# 8_RGB_SMD_LEDs.net
KiCad netlist of a schematic drawn in EAGLE
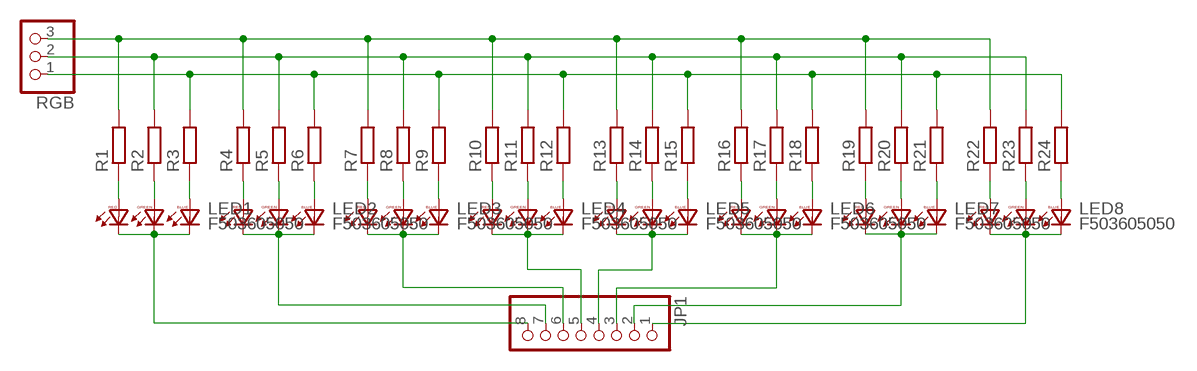
[diagram p0: schematic, sheet 1]

(export (version "E")
  (design (tool "Eeschema 10.0.6"))
  (components
    (comp (ref "JP1")
      (value "PINHD-1X8")
      (footprint "eagle-import:1X08")
      (libsource (lib "eagle-import") (part "PINHD-1X8"))
    )
    (comp (ref "LED1")
      (value "F503605050")
      (footprint "eagle-import:5050LED")
      (libsource (lib "eagle-import") (part "F503605050"))
    )
    (comp (ref "LED2")
      (value "F503605050")
      (footprint "eagle-import:5050LED")
      (libsource (lib "eagle-import") (part "F503605050"))
    )
    (comp (ref "LED3")
      (value "F503605050")
      (footprint "eagle-import:5050LED")
      (libsource (lib "eagle-import") (part "F503605050"))
    )
    (comp (ref "LED4")
      (value "F503605050")
      (footprint "eagle-import:5050LED")
      (libsource (lib "eagle-import") (part "F503605050"))
    )
    (comp (ref "LED5")
      (value "F503605050")
      (footprint "eagle-import:5050LED")
      (libsource (lib "eagle-import") (part "F503605050"))
    )
    (comp (ref "LED6")
      (value "F503605050")
      (footprint "eagle-import:5050LED")
      (libsource (lib "eagle-import") (part "F503605050"))
    )
    (comp (ref "LED7")
      (value "F503605050")
      (footprint "eagle-import:5050LED")
      (libsource (lib "eagle-import") (part "F503605050"))
    )
    (comp (ref "LED8")
      (value "F503605050")
      (footprint "eagle-import:5050LED")
      (libsource (lib "eagle-import") (part "F503605050"))
    )
    (comp (ref "R1")
      (value "R-EU_0207/7")
      (footprint "eagle-import:0207_7")
      (libsource (lib "eagle-import") (part "R-EU_0207/7"))
    )
    (comp (ref "R2")
      (value "R-EU_0207/7")
      (footprint "eagle-import:0207_7")
      (libsource (lib "eagle-import") (part "R-EU_0207/7"))
    )
    (comp (ref "R3")
      (value "R-EU_0207/7")
      (footprint "eagle-import:0207_7")
      (libsource (lib "eagle-import") (part "R-EU_0207/7"))
    )
    (comp (ref "R4")
      (value "R-EU_0207/7")
      (footprint "eagle-import:0207_7")
      (libsource (lib "eagle-import") (part "R-EU_0207/7"))
    )
    (comp (ref "R5")
      (value "R-EU_0207/7")
      (footprint "eagle-import:0207_7")
      (libsource (lib "eagle-import") (part "R-EU_0207/7"))
    )
    (comp (ref "R6")
      (value "R-EU_0207/7")
      (footprint "eagle-import:0207_7")
      (libsource (lib "eagle-import") (part "R-EU_0207/7"))
    )
    (comp (ref "R7")
      (value "R-EU_0207/7")
      (footprint "eagle-import:0207_7")
      (libsource (lib "eagle-import") (part "R-EU_0207/7"))
    )
    (comp (ref "R8")
      (value "R-EU_0207/7")
      (footprint "eagle-import:0207_7")
      (libsource (lib "eagle-import") (part "R-EU_0207/7"))
    )
    (comp (ref "R9")
      (value "R-EU_0207/7")
      (footprint "eagle-import:0207_7")
      (libsource (lib "eagle-import") (part "R-EU_0207/7"))
    )
    (comp (ref "R10")
      (value "R-EU_0207/7")
      (footprint "eagle-import:0207_7")
      (libsource (lib "eagle-import") (part "R-EU_0207/7"))
    )
    (comp (ref "R11")
      (value "R-EU_0207/7")
      (footprint "eagle-import:0207_7")
      (libsource (lib "eagle-import") (part "R-EU_0207/7"))
    )
    (comp (ref "R12")
      (value "R-EU_0207/7")
      (footprint "eagle-import:0207_7")
      (libsource (lib "eagle-import") (part "R-EU_0207/7"))
    )
    (comp (ref "R13")
      (value "R-EU_0207/7")
      (footprint "eagle-import:0207_7")
      (libsource (lib "eagle-import") (part "R-EU_0207/7"))
    )
    (comp (ref "R14")
      (value "R-EU_0207/7")
      (footprint "eagle-import:0207_7")
      (libsource (lib "eagle-import") (part "R-EU_0207/7"))
    )
    (comp (ref "R15")
      (value "R-EU_0207/7")
      (footprint "eagle-import:0207_7")
      (libsource (lib "eagle-import") (part "R-EU_0207/7"))
    )
    (comp (ref "R16")
      (value "R-EU_0207/7")
      (footprint "eagle-import:0207_7")
      (libsource (lib "eagle-import") (part "R-EU_0207/7"))
    )
    (comp (ref "R17")
      (value "R-EU_0207/7")
      (footprint "eagle-import:0207_7")
      (libsource (lib "eagle-import") (part "R-EU_0207/7"))
    )
    (comp (ref "R18")
      (value "R-EU_0207/7")
      (footprint "eagle-import:0207_7")
      (libsource (lib "eagle-import") (part "R-EU_0207/7"))
    )
    (comp (ref "R19")
      (value "R-EU_0207/7")
      (footprint "eagle-import:0207_7")
      (libsource (lib "eagle-import") (part "R-EU_0207/7"))
    )
    (comp (ref "R20")
      (value "R-EU_0207/7")
      (footprint "eagle-import:0207_7")
      (libsource (lib "eagle-import") (part "R-EU_0207/7"))
    )
    (comp (ref "R21")
      (value "R-EU_0207/7")
      (footprint "eagle-import:0207_7")
      (libsource (lib "eagle-import") (part "R-EU_0207/7"))
    )
    (comp (ref "R22")
      (value "R-EU_0207/7")
      (footprint "eagle-import:0207_7")
      (libsource (lib "eagle-import") (part "R-EU_0207/7"))
    )
    (comp (ref "R23")
      (value "R-EU_0207/7")
      (footprint "eagle-import:0207_7")
      (libsource (lib "eagle-import") (part "R-EU_0207/7"))
    )
    (comp (ref "R24")
      (value "R-EU_0207/7")
      (footprint "eagle-import:0207_7")
      (libsource (lib "eagle-import") (part "R-EU_0207/7"))
    )
    (comp (ref "RGB")
      (value "PINHD-1X3")
      (footprint "eagle-import:1X03")
      (libsource (lib "eagle-import") (part "PINHD-1X3"))
    )
  )
  (nets
    (net (code "1") (name "Net-(LED1-BA)") (class "Default")
      (node (ref "LED1") (pin "B1") (pinfunction "BA_B1") (pintype "passive"))
      (node (ref "R3") (pin "1") (pinfunction "1_1") (pintype "passive"))
    )
    (net (code "2") (name "Net-(LED1-BC)") (class "Default")
      (node (ref "JP1") (pin "8") (pinfunction "8_8") (pintype "passive"))
      (node (ref "LED1") (pin "B2") (pinfunction "BC_B2") (pintype "passive"))
      (node (ref "LED1") (pin "G2") (pinfunction "GC_G2") (pintype "passive"))
      (node (ref "LED1") (pin "R2") (pinfunction "RC_R2") (pintype "passive"))
    )
    (net (code "3") (name "Net-(LED1-GA)") (class "Default")
      (node (ref "LED1") (pin "G1") (pinfunction "GA_G1") (pintype "passive"))
      (node (ref "R2") (pin "1") (pinfunction "1_1") (pintype "passive"))
    )
    (net (code "4") (name "Net-(LED1-RA)") (class "Default")
      (node (ref "LED1") (pin "R1") (pinfunction "RA_R1") (pintype "passive"))
      (node (ref "R1") (pin "1") (pinfunction "1_1") (pintype "passive"))
    )
    (net (code "5") (name "Net-(LED2-BA)") (class "Default")
      (node (ref "LED2") (pin "B1") (pinfunction "BA_B1") (pintype "passive"))
      (node (ref "R6") (pin "1") (pinfunction "1_1") (pintype "passive"))
    )
    (net (code "6") (name "Net-(LED2-BC)") (class "Default")
      (node (ref "JP1") (pin "7") (pinfunction "7_7") (pintype "passive"))
      (node (ref "LED2") (pin "B2") (pinfunction "BC_B2") (pintype "passive"))
      (node (ref "LED2") (pin "G2") (pinfunction "GC_G2") (pintype "passive"))
      (node (ref "LED2") (pin "R2") (pinfunction "RC_R2") (pintype "passive"))
    )
    (net (code "7") (name "Net-(LED2-GA)") (class "Default")
      (node (ref "LED2") (pin "G1") (pinfunction "GA_G1") (pintype "passive"))
      (node (ref "R5") (pin "1") (pinfunction "1_1") (pintype "passive"))
    )
    (net (code "8") (name "Net-(LED2-RA)") (class "Default")
      (node (ref "LED2") (pin "R1") (pinfunction "RA_R1") (pintype "passive"))
      (node (ref "R4") (pin "1") (pinfunction "1_1") (pintype "passive"))
    )
    (net (code "9") (name "Net-(LED3-BA)") (class "Default")
      (node (ref "LED3") (pin "B1") (pinfunction "BA_B1") (pintype "passive"))
      (node (ref "R9") (pin "1") (pinfunction "1_1") (pintype "passive"))
    )
    (net (code "10") (name "Net-(LED3-BC)") (class "Default")
      (node (ref "JP1") (pin "6") (pinfunction "6_6") (pintype "passive"))
      (node (ref "LED3") (pin "B2") (pinfunction "BC_B2") (pintype "passive"))
      (node (ref "LED3") (pin "G2") (pinfunction "GC_G2") (pintype "passive"))
      (node (ref "LED3") (pin "R2") (pinfunction "RC_R2") (pintype "passive"))
    )
    (net (code "11") (name "Net-(LED3-GA)") (class "Default")
      (node (ref "LED3") (pin "G1") (pinfunction "GA_G1") (pintype "passive"))
      (node (ref "R8") (pin "1") (pinfunction "1_1") (pintype "passive"))
    )
    (net (code "12") (name "Net-(LED3-RA)") (class "Default")
      (node (ref "LED3") (pin "R1") (pinfunction "RA_R1") (pintype "passive"))
      (node (ref "R7") (pin "1") (pinfunction "1_1") (pintype "passive"))
    )
    (net (code "13") (name "Net-(LED4-BA)") (class "Default")
      (node (ref "LED4") (pin "B1") (pinfunction "BA_B1") (pintype "passive"))
      (node (ref "R12") (pin "1") (pinfunction "1_1") (pintype "passive"))
    )
    (net (code "14") (name "Net-(LED4-BC)") (class "Default")
      (node (ref "JP1") (pin "5") (pinfunction "5_5") (pintype "passive"))
      (node (ref "LED4") (pin "B2") (pinfunction "BC_B2") (pintype "passive"))
      (node (ref "LED4") (pin "G2") (pinfunction "GC_G2") (pintype "passive"))
      (node (ref "LED4") (pin "R2") (pinfunction "RC_R2") (pintype "passive"))
    )
    (net (code "15") (name "Net-(LED4-GA)") (class "Default")
      (node (ref "LED4") (pin "G1") (pinfunction "GA_G1") (pintype "passive"))
      (node (ref "R11") (pin "1") (pinfunction "1_1") (pintype "passive"))
    )
    (net (code "16") (name "Net-(LED4-RA)") (class "Default")
      (node (ref "LED4") (pin "R1") (pinfunction "RA_R1") (pintype "passive"))
      (node (ref "R10") (pin "1") (pinfunction "1_1") (pintype "passive"))
    )
    (net (code "17") (name "Net-(LED5-BA)") (class "Default")
      (node (ref "LED5") (pin "B1") (pinfunction "BA_B1") (pintype "passive"))
      (node (ref "R15") (pin "1") (pinfunction "1_1") (pintype "passive"))
    )
    (net (code "18") (name "Net-(LED5-BC)") (class "Default")
      (node (ref "JP1") (pin "4") (pinfunction "4_4") (pintype "passive"))
      (node (ref "LED5") (pin "B2") (pinfunction "BC_B2") (pintype "passive"))
      (node (ref "LED5") (pin "G2") (pinfunction "GC_G2") (pintype "passive"))
      (node (ref "LED5") (pin "R2") (pinfunction "RC_R2") (pintype "passive"))
    )
    (net (code "19") (name "Net-(LED5-GA)") (class "Default")
      (node (ref "LED5") (pin "G1") (pinfunction "GA_G1") (pintype "passive"))
      (node (ref "R14") (pin "1") (pinfunction "1_1") (pintype "passive"))
    )
    (net (code "20") (name "Net-(LED5-RA)") (class "Default")
      (node (ref "LED5") (pin "R1") (pinfunction "RA_R1") (pintype "passive"))
      (node (ref "R13") (pin "1") (pinfunction "1_1") (pintype "passive"))
    )
    (net (code "21") (name "Net-(LED6-BA)") (class "Default")
      (node (ref "LED6") (pin "B1") (pinfunction "BA_B1") (pintype "passive"))
      (node (ref "R18") (pin "1") (pinfunction "1_1") (pintype "passive"))
    )
    (net (code "22") (name "Net-(LED6-BC)") (class "Default")
      (node (ref "JP1") (pin "3") (pinfunction "3_3") (pintype "passive"))
      (node (ref "LED6") (pin "B2") (pinfunction "BC_B2") (pintype "passive"))
      (node (ref "LED6") (pin "G2") (pinfunction "GC_G2") (pintype "passive"))
      (node (ref "LED6") (pin "R2") (pinfunction "RC_R2") (pintype "passive"))
    )
    (net (code "23") (name "Net-(LED6-GA)") (class "Default")
      (node (ref "LED6") (pin "G1") (pinfunction "GA_G1") (pintype "passive"))
      (node (ref "R17") (pin "1") (pinfunction "1_1") (pintype "passive"))
    )
    (net (code "24") (name "Net-(LED6-RA)") (class "Default")
      (node (ref "LED6") (pin "R1") (pinfunction "RA_R1") (pintype "passive"))
      (node (ref "R16") (pin "1") (pinfunction "1_1") (pintype "passive"))
    )
    (net (code "25") (name "Net-(LED7-BA)") (class "Default")
      (node (ref "LED7") (pin "B1") (pinfunction "BA_B1") (pintype "passive"))
      (node (ref "R21") (pin "1") (pinfunction "1_1") (pintype "passive"))
    )
    (net (code "26") (name "Net-(LED7-BC)") (class "Default")
      (node (ref "JP1") (pin "2") (pinfunction "2_2") (pintype "passive"))
      (node (ref "LED7") (pin "B2") (pinfunction "BC_B2") (pintype "passive"))
      (node (ref "LED7") (pin "G2") (pinfunction "GC_G2") (pintype "passive"))
      (node (ref "LED7") (pin "R2") (pinfunction "RC_R2") (pintype "passive"))
    )
    (net (code "27") (name "Net-(LED7-GA)") (class "Default")
      (node (ref "LED7") (pin "G1") (pinfunction "GA_G1") (pintype "passive"))
      (node (ref "R20") (pin "1") (pinfunction "1_1") (pintype "passive"))
    )
    (net (code "28") (name "Net-(LED7-RA)") (class "Default")
      (node (ref "LED7") (pin "R1") (pinfunction "RA_R1") (pintype "passive"))
      (node (ref "R19") (pin "1") (pinfunction "1_1") (pintype "passive"))
    )
    (net (code "29") (name "Net-(LED8-BA)") (class "Default")
      (node (ref "LED8") (pin "B1") (pinfunction "BA_B1") (pintype "passive"))
      (node (ref "R24") (pin "1") (pinfunction "1_1") (pintype "passive"))
    )
    (net (code "30") (name "Net-(LED8-BC)") (class "Default")
      (node (ref "JP1") (pin "1") (pinfunction "1_1") (pintype "passive"))
      (node (ref "LED8") (pin "B2") (pinfunction "BC_B2") (pintype "passive"))
      (node (ref "LED8") (pin "G2") (pinfunction "GC_G2") (pintype "passive"))
      (node (ref "LED8") (pin "R2") (pinfunction "RC_R2") (pintype "passive"))
    )
    (net (code "31") (name "Net-(LED8-GA)") (class "Default")
      (node (ref "LED8") (pin "G1") (pinfunction "GA_G1") (pintype "passive"))
      (node (ref "R23") (pin "1") (pinfunction "1_1") (pintype "passive"))
    )
    (net (code "32") (name "Net-(LED8-RA)") (class "Default")
      (node (ref "LED8") (pin "R1") (pinfunction "RA_R1") (pintype "passive"))
      (node (ref "R22") (pin "1") (pinfunction "1_1") (pintype "passive"))
    )
    (net (code "33") (name "Net-(R1-Pad2)") (class "Default")
      (node (ref "R1") (pin "2") (pinfunction "2_2") (pintype "passive"))
      (node (ref "R10") (pin "2") (pinfunction "2_2") (pintype "passive"))
      (node (ref "R13") (pin "2") (pinfunction "2_2") (pintype "passive"))
      (node (ref "R16") (pin "2") (pinfunction "2_2") (pintype "passive"))
      (node (ref "R19") (pin "2") (pinfunction "2_2") (pintype "passive"))
      (node (ref "R22") (pin "2") (pinfunction "2_2") (pintype "passive"))
      (node (ref "R4") (pin "2") (pinfunction "2_2") (pintype "passive"))
      (node (ref "R7") (pin "2") (pinfunction "2_2") (pintype "passive"))
      (node (ref "RGB") (pin "3") (pinfunction "3_3") (pintype "passive"))
    )
    (net (code "34") (name "Net-(R11-Pad2)") (class "Default")
      (node (ref "R11") (pin "2") (pinfunction "2_2") (pintype "passive"))
      (node (ref "R14") (pin "2") (pinfunction "2_2") (pintype "passive"))
      (node (ref "R17") (pin "2") (pinfunction "2_2") (pintype "passive"))
      (node (ref "R2") (pin "2") (pinfunction "2_2") (pintype "passive"))
      (node (ref "R20") (pin "2") (pinfunction "2_2") (pintype "passive"))
      (node (ref "R23") (pin "2") (pinfunction "2_2") (pintype "passive"))
      (node (ref "R5") (pin "2") (pinfunction "2_2") (pintype "passive"))
      (node (ref "R8") (pin "2") (pinfunction "2_2") (pintype "passive"))
      (node (ref "RGB") (pin "2") (pinfunction "2_2") (pintype "passive"))
    )
    (net (code "35") (name "Net-(R12-Pad2)") (class "Default")
      (node (ref "R12") (pin "2") (pinfunction "2_2") (pintype "passive"))
      (node (ref "R15") (pin "2") (pinfunction "2_2") (pintype "passive"))
      (node (ref "R18") (pin "2") (pinfunction "2_2") (pintype "passive"))
      (node (ref "R21") (pin "2") (pinfunction "2_2") (pintype "passive"))
      (node (ref "R24") (pin "2") (pinfunction "2_2") (pintype "passive"))
      (node (ref "R3") (pin "2") (pinfunction "2_2") (pintype "passive"))
      (node (ref "R6") (pin "2") (pinfunction "2_2") (pintype "passive"))
      (node (ref "R9") (pin "2") (pinfunction "2_2") (pintype "passive"))
      (node (ref "RGB") (pin "1") (pinfunction "1_1") (pintype "passive"))
    )
  )
)
